# 4_-Analog_Input.net
KiCad netlist of a schematic drawn in Altium Designer
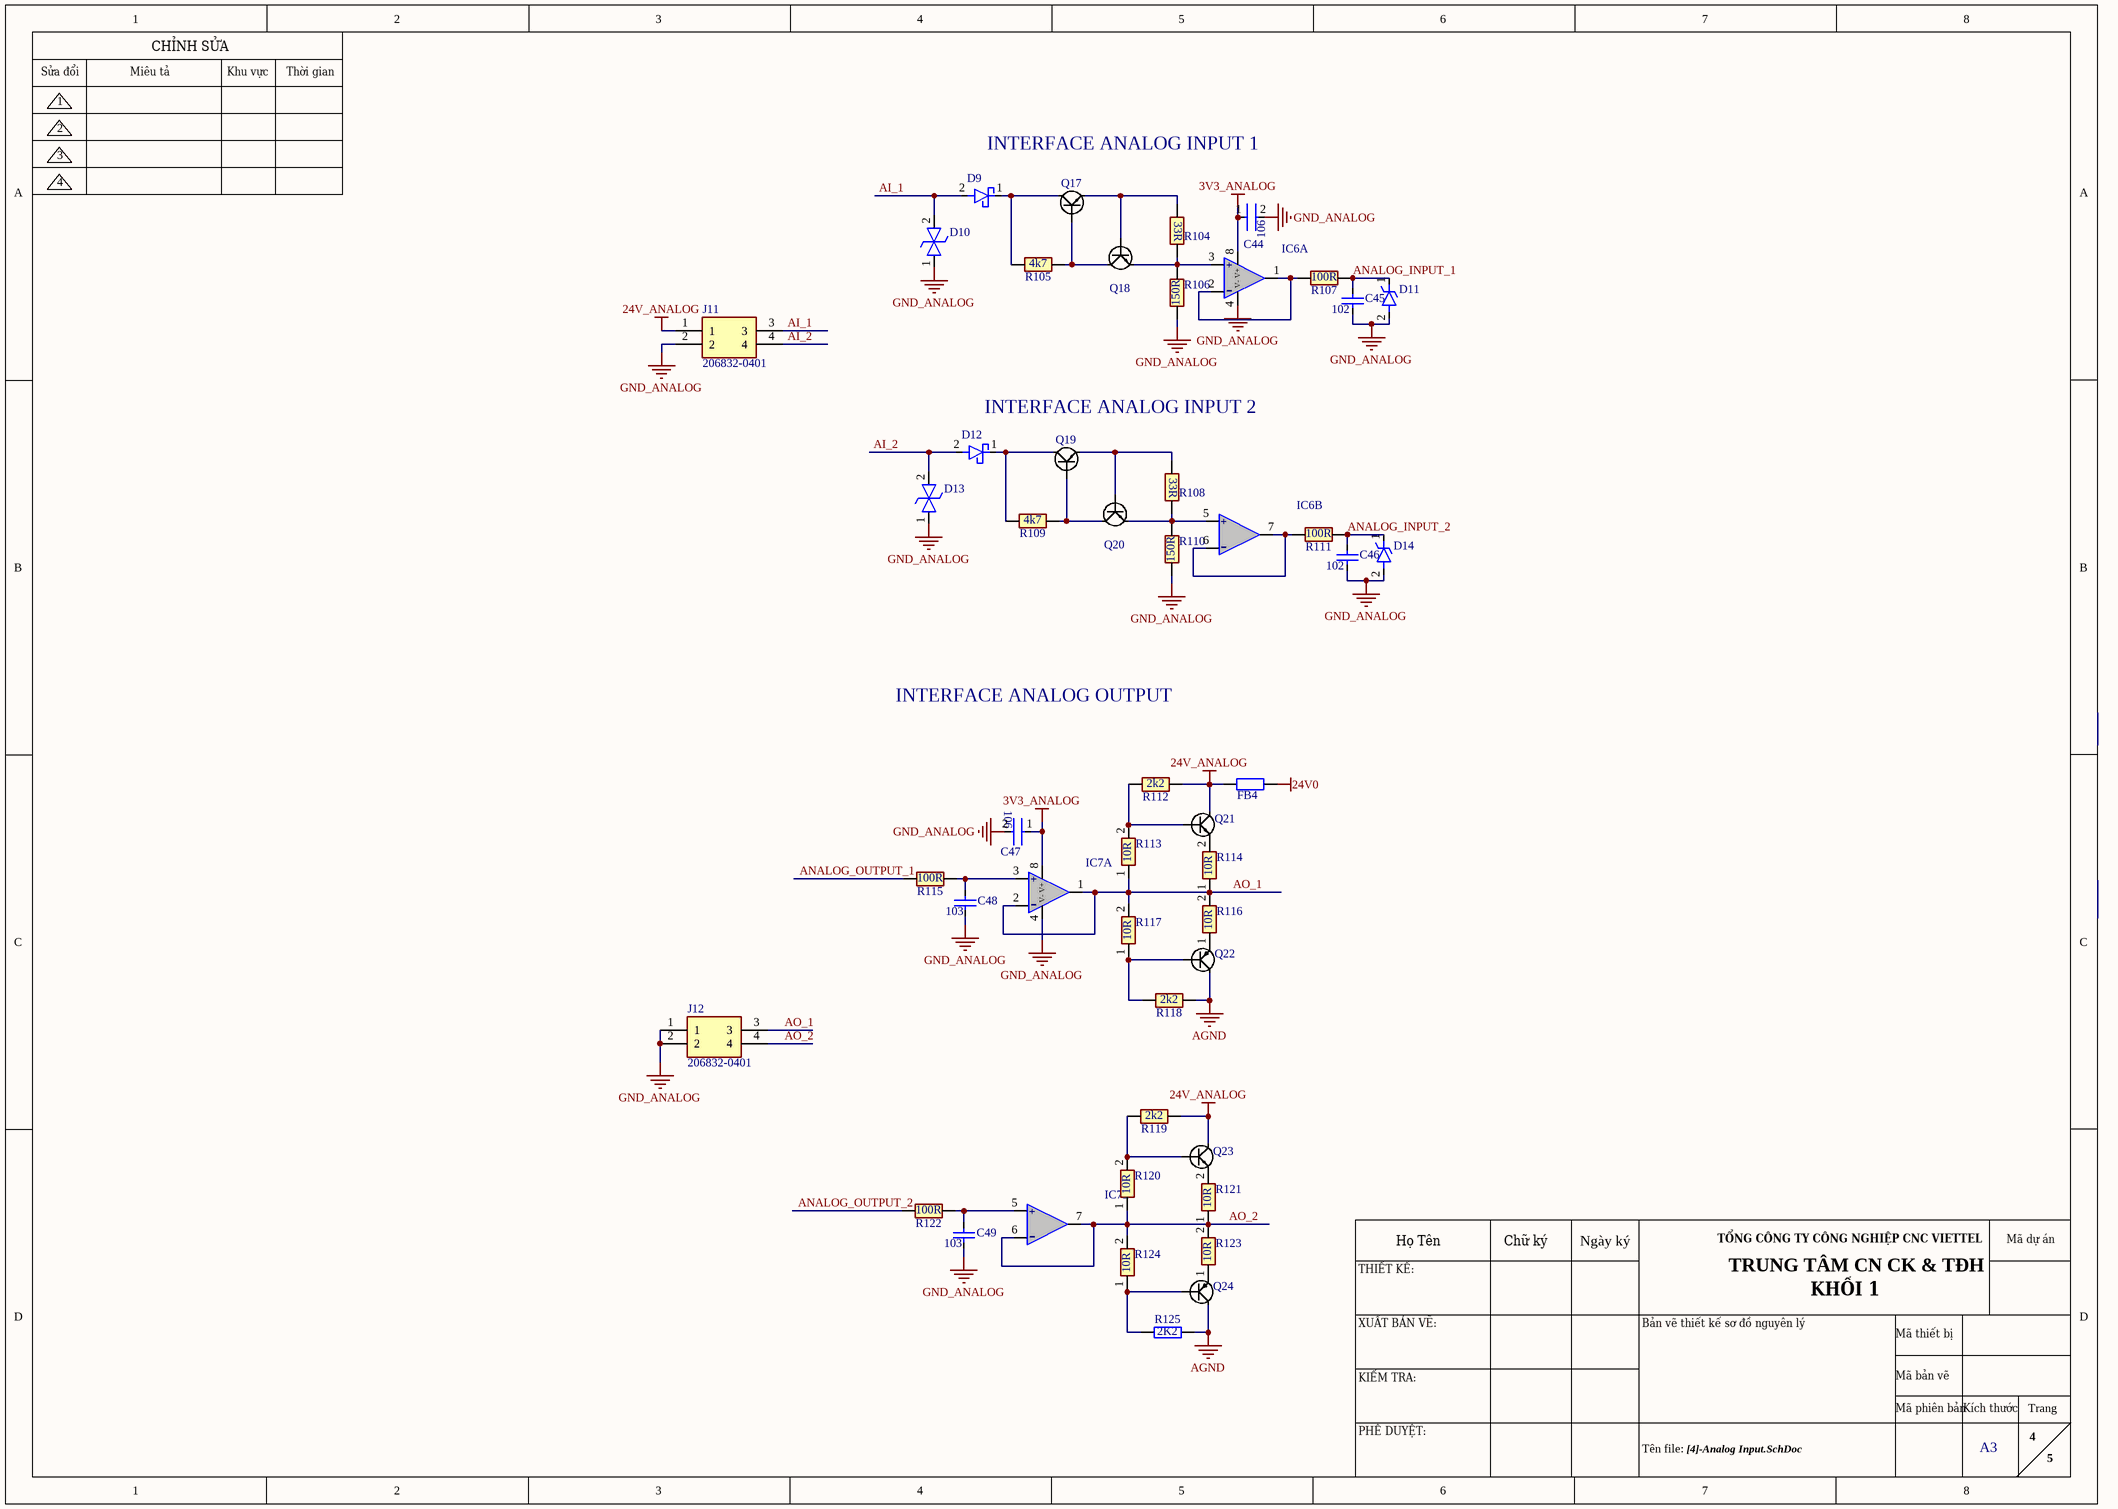
[diagram p0: [4]-Analog Input.SchDoc]

(export (version "E")
  (design (tool "Eeschema 10.0.6"))
  (components
    (comp (ref "C44")
      (value "C0603_106_35V")
      (footprint "SamacSys:C0603")
      (description "Multilayer Ceramic Capacitors MLCC - SMD/SMT 10 uF 35 VDC 20% 0603 X5R")
      (fields
        (field (name "MANUFACTURER_PART_NUMBER") "GRM188R6YA106MA73J")
        (field (name "MOUSER PART NUMBER") "81-GRM188R6YA106MA3J")
      )
      (libsource (lib "SamacSys") (part "C0603_106_35V"))
    )
    (comp (ref "C45")
      (value "C0603_102_50V")
      (footprint "SamacSys:C0603")
      (description "Multilayer Ceramic Capacitors MLCC - SMD/SMT 50V 1000pF X7R 0603 10%")
      (fields
        (field (name "MANUFACTURER_PART_NUMBER") "CC0603KRX7R9BB102")
        (field (name "MOUSER PART NUMBER") "603-CC603KRX7R9BB102")
      )
      (libsource (lib "SamacSys") (part "C0603_102_50V"))
    )
    (comp (ref "C46")
      (value "C0603_102_50V")
      (footprint "SamacSys:C0603")
      (description "Multilayer Ceramic Capacitors MLCC - SMD/SMT 50V 1000pF X7R 0603 10%")
      (fields
        (field (name "MANUFACTURER_PART_NUMBER") "CC0603KRX7R9BB102")
        (field (name "MOUSER PART NUMBER") "603-CC603KRX7R9BB102")
      )
      (libsource (lib "SamacSys") (part "C0603_102_50V"))
    )
    (comp (ref "C47")
      (value "C0603_106_35V")
      (footprint "SamacSys:C0603")
      (description "Multilayer Ceramic Capacitors MLCC - SMD/SMT 10 uF 35 VDC 20% 0603 X5R")
      (fields
        (field (name "MANUFACTURER_PART_NUMBER") "GRM188R6YA106MA73J")
        (field (name "MOUSER PART NUMBER") "81-GRM188R6YA106MA3J")
      )
      (libsource (lib "SamacSys") (part "C0603_106_35V"))
    )
    (comp (ref "C48")
      (value "C0603_103_50V")
      (footprint "SamacSys:C0603")
      (description "Multilayer Ceramic Capacitors MLCC - SMD/SMT 50V 0.01uF X7R 0603 10%")
      (fields
        (field (name "MANUFACTURER_PART_NUMBER") "CC0603KRX7R9BB103")
        (field (name "MOUSER PART NUMBER") "603-CC603KRX7R9BB103")
      )
      (libsource (lib "SamacSys") (part "C0603_103_50V"))
    )
    (comp (ref "C49")
      (value "C0603_103_50V")
      (footprint "SamacSys:C0603")
      (description "Multilayer Ceramic Capacitors MLCC - SMD/SMT 50V 0.01uF X7R 0603 10%")
      (fields
        (field (name "MANUFACTURER_PART_NUMBER") "CC0603KRX7R9BB103")
        (field (name "MOUSER PART NUMBER") "603-CC603KRX7R9BB103")
      )
      (libsource (lib "SamacSys") (part "C0603_103_50V"))
    )
    (comp (ref "D9")
      (value "SS36FA")
      (footprint "SamacSys:SOD-123FA-2")
      (description "Schottky Diodes & Rectifiers 60V 3A Schottky B arrier Rectifier")
      (fields (field (name "MOUSER PART NUMBER") "512-SS36FA"))
      (libsource (lib "SamacSys") (part "SS36FA"))
    )
    (comp (ref "D10")
      (value "SMCJ36CA_V6G")
      (footprint "SamacSys:DIONM7959X262N")
      (description "TVS Diode (Bi-directional)")
      (fields
        (field (name "MANUFACTURER_PART_NUMBER") "SMCJ36CA V6G")
        (field (name "MOUSER PART NUMBER") "821-SMCJ36CAV6G")
      )
      (libsource (lib "SamacSys") (part "SMCJ36CA_V6G"))
    )
    (comp (ref "D11")
      (value "MM3Z3V3B")
      (footprint "SamacSys:SOD323F")
      (description "Zener Diodes 3.3V 200mW 2%")
      (fields (field (name "MOUSER PART NUMBER") "512-MM3Z3V3B"))
      (libsource (lib "SamacSys") (part "MM3Z3V3B"))
    )
    (comp (ref "D12")
      (value "SS36FA")
      (footprint "SamacSys:SOD-123FA-2")
      (description "Schottky Diodes & Rectifiers 60V 3A Schottky B arrier Rectifier")
      (fields (field (name "MOUSER PART NUMBER") "512-SS36FA"))
      (libsource (lib "SamacSys") (part "SS36FA"))
    )
    (comp (ref "D13")
      (value "SMCJ36CA_V6G")
      (footprint "SamacSys:DIONM7959X262N")
      (description "TVS Diode (Bi-directional)")
      (fields
        (field (name "MANUFACTURER_PART_NUMBER") "SMCJ36CA V6G")
        (field (name "MOUSER PART NUMBER") "821-SMCJ36CAV6G")
      )
      (libsource (lib "SamacSys") (part "SMCJ36CA_V6G"))
    )
    (comp (ref "D14")
      (value "MM3Z3V3B")
      (footprint "SamacSys:SOD323F")
      (description "Zener Diodes 3.3V 200mW 2%")
      (fields (field (name "MOUSER PART NUMBER") "512-MM3Z3V3B"))
      (libsource (lib "SamacSys") (part "MM3Z3V3B"))
    )
    (comp (ref "FB4")
      (value "FERRIT_0805_1A")
      (footprint "SamacSys:FB0805")
      (fields
        (field (name "MANUFACTURER") "Laird-Signal Integrity Products")
        (field (name "PART NUMBER") "MI0805J102R-10")
      )
      (libsource (lib "SamacSys") (part "FERRIT_0805_1A"))
    )
    (comp (ref "IC6")
      (value "LM358DGKR")
      (footprint "SamacSys:VSSOP-8")
      (description "Integrated Circuit")
      (fields (field (name "MOUSER PART NUMBER") "595-LM358DGKR"))
      (libsource (lib "SamacSys") (part "LM358DGKR"))
    )
    (comp (ref "IC7")
      (value "LM358DGKR")
      (footprint "SamacSys:VSSOP-8")
      (description "Integrated Circuit")
      (fields (field (name "MOUSER PART NUMBER") "595-LM358DGKR"))
      (libsource (lib "SamacSys") (part "LM358DGKR"))
    )
    (comp (ref "J11")
      (value "206832-0401")
      (footprint "2068320401")
      (description "Headers & Wire Housings Micro-Fit Plus Vert HDR ASSY 2X2 Tin Lu")
      (fields (field (name "MOUSER PART NUMBER") "538-206832-0401"))
      (libsource (lib "SamacSys") (part "Header_2x2_male"))
    )
    (comp (ref "J12")
      (value "206832-0401")
      (footprint "2068320401")
      (description "Headers & Wire Housings Micro-Fit Plus Vert HDR ASSY 2X2 Tin Lu")
      (fields (field (name "MOUSER PART NUMBER") "538-206832-0401"))
      (libsource (lib "SamacSys") (part "Header_2x2_male"))
    )
    (comp (ref "Q17")
      (value "MMBT3904-TP")
      (footprint "SamacSys:SOT-23-3")
      (description "Transistor BJT NPN")
      (fields (field (name "MOUSER PART NUMBER") "833-MMBT3904-TP"))
      (libsource (lib "SamacSys") (part "MMBT3904-TP"))
    )
    (comp (ref "Q18")
      (value "MMBT3904-TP")
      (footprint "SamacSys:SOT-23-3")
      (description "Transistor BJT NPN")
      (fields (field (name "MOUSER PART NUMBER") "833-MMBT3904-TP"))
      (libsource (lib "SamacSys") (part "MMBT3904-TP"))
    )
    (comp (ref "Q19")
      (value "MMBT3904-TP")
      (footprint "SamacSys:SOT-23-3")
      (description "Transistor BJT NPN")
      (fields (field (name "MOUSER PART NUMBER") "833-MMBT3904-TP"))
      (libsource (lib "SamacSys") (part "MMBT3904-TP"))
    )
    (comp (ref "Q20")
      (value "MMBT3904-TP")
      (footprint "SamacSys:SOT-23-3")
      (description "Transistor BJT NPN")
      (fields (field (name "MOUSER PART NUMBER") "833-MMBT3904-TP"))
      (libsource (lib "SamacSys") (part "MMBT3904-TP"))
    )
    (comp (ref "Q21")
      (value "PMBT2222A,215")
      (footprint "SOT-23")
      (description "Bipolar (BJT) Transistor NPN 30 V 600 mA 300MHz 250 mW Surface Mount TO-236AB")
      (fields (field (name "MANUFACTURER") "Nexperia USA Inc."))
      (libsource (lib "SamacSys") (part "PMBT2222A,215"))
    )
    (comp (ref "Q22")
      (value "PMBT2907A,215")
      (footprint "SOT-23")
      (description "Bipolar (BJT) Transistor PNP 60 V 600 mA 200MHz 250 mW Surface Mount TO-236AB")
      (fields (field (name "MANUFACTURER") "Nexperia USA Inc."))
      (libsource (lib "SamacSys") (part "PMBT2907A,215"))
    )
    (comp (ref "Q23")
      (value "PMBT2222A,215")
      (footprint "SOT-23")
      (description "Bipolar (BJT) Transistor NPN 30 V 600 mA 300MHz 250 mW Surface Mount TO-236AB")
      (fields (field (name "MANUFACTURER") "Nexperia USA Inc."))
      (libsource (lib "SamacSys") (part "PMBT2222A,215"))
    )
    (comp (ref "Q24")
      (value "PMBT2907A,215")
      (footprint "SOT-23")
      (description "Bipolar (BJT) Transistor PNP 60 V 600 mA 200MHz 250 mW Surface Mount TO-236AB")
      (fields (field (name "MANUFACTURER") "Nexperia USA Inc."))
      (libsource (lib "SamacSys") (part "PMBT2907A,215"))
    )
    (comp (ref "R104")
      (value "R0603_33R")
      (footprint "SamacSys:RES-SMD-0603")
      (description "Resistor")
      (fields
        (field (name "MANUFACTURER_PART_NUMBER") "RC0603FR-0733RL")
        (field (name "MOUSER PART NUMBER") "603-RC0603FR-0733RL")
      )
      (libsource (lib "SamacSys") (part "R0603_33R"))
    )
    (comp (ref "R105")
      (value "R0603_4k7")
      (footprint "SamacSys:RES-SMD-0603")
      (description "Resistor")
      (fields
        (field (name "MANUFACTURER_PART_NUMBER") "ERJ-U3RD4701V")
        (field (name "MOUSER PART NUMBER") "667-ERJ-U3RD4701V")
      )
      (libsource (lib "SamacSys") (part "R0603_4k7"))
    )
    (comp (ref "R106")
      (value "R0603_150R")
      (footprint "SamacSys:RES-SMD-0603")
      (description "Resistor")
      (fields
        (field (name "MANUFACTURER_PART_NUMBER") "ERA-3AEB151V")
        (field (name "MOUSER PART NUMBER") "667-ERA-3AEB151V")
      )
      (libsource (lib "SamacSys") (part "R0603_150R"))
    )
    (comp (ref "R107")
      (value "100R")
      (footprint "SamacSys:RES-SMD-0603")
      (description "Thick Film Resistors - SMD 1/10watt 100ohms 5%")
      (fields
        (field (name "MANUFACTURER_PART_NUMBER") "CRCW0603100RJNEB")
        (field (name "MOUSER PART NUMBER") "71-CRCW0603100RJNEB")
      )
      (libsource (lib "SamacSys") (part "R0603_100R_75V"))
    )
    (comp (ref "R108")
      (value "R0603_33R")
      (footprint "SamacSys:RES-SMD-0603")
      (description "Resistor")
      (fields
        (field (name "MANUFACTURER_PART_NUMBER") "RC0603FR-0733RL")
        (field (name "MOUSER PART NUMBER") "603-RC0603FR-0733RL")
      )
      (libsource (lib "SamacSys") (part "R0603_33R"))
    )
    (comp (ref "R109")
      (value "R0603_4k7")
      (footprint "SamacSys:RES-SMD-0603")
      (description "Resistor")
      (fields
        (field (name "MANUFACTURER_PART_NUMBER") "ERJ-U3RD4701V")
        (field (name "MOUSER PART NUMBER") "667-ERJ-U3RD4701V")
      )
      (libsource (lib "SamacSys") (part "R0603_4k7"))
    )
    (comp (ref "R110")
      (value "R0603_150R")
      (footprint "SamacSys:RES-SMD-0603")
      (description "Resistor")
      (fields
        (field (name "MANUFACTURER_PART_NUMBER") "ERA-3AEB151V")
        (field (name "MOUSER PART NUMBER") "667-ERA-3AEB151V")
      )
      (libsource (lib "SamacSys") (part "R0603_150R"))
    )
    (comp (ref "R111")
      (value "100R")
      (footprint "SamacSys:RES-SMD-0603")
      (description "Thick Film Resistors - SMD 1/10watt 100ohms 5%")
      (fields
        (field (name "MANUFACTURER_PART_NUMBER") "CRCW0603100RJNEB")
        (field (name "MOUSER PART NUMBER") "71-CRCW0603100RJNEB")
      )
      (libsource (lib "SamacSys") (part "R0603_100R_75V"))
    )
    (comp (ref "R112")
      (value "R0603_2k2")
      (footprint "RES-SMD-0603")
      (description "Resistor")
      (fields
        (field (name "MANUFACTURER_PART_NUMBER") "ERJ-3EKF2201V")
        (field (name "MOUSER PART NUMBER") "667-ERJ-3EKF2201V")
      )
      (libsource (lib "SamacSys") (part "R0603_2k2"))
    )
    (comp (ref "R113")
      (value "R0603_10R")
      (footprint "SamacSys:RES-SMD-0603")
      (description "Thick Film Resistors - SMD 0603 10ohm 1% Anti-Surge AEC-Q200")
      (fields
        (field (name "MANUFACTURER_PART_NUMBER") "ERJ-PA3F10R0V")
        (field (name "MOUSER PART NUMBER") "667-ERJ-PA3F10R0V")
      )
      (libsource (lib "SamacSys") (part "R0603_10R"))
    )
    (comp (ref "R114")
      (value "R0603_10R")
      (footprint "SamacSys:RES-SMD-0603")
      (description "Thick Film Resistors - SMD 0603 10ohm 1% Anti-Surge AEC-Q200")
      (fields
        (field (name "MANUFACTURER_PART_NUMBER") "ERJ-PA3F10R0V")
        (field (name "MOUSER PART NUMBER") "667-ERJ-PA3F10R0V")
      )
      (libsource (lib "SamacSys") (part "R0603_10R"))
    )
    (comp (ref "R115")
      (value "100R")
      (footprint "SamacSys:RES-SMD-0603")
      (description "Thick Film Resistors - SMD 1/10watt 100ohms 5%")
      (fields
        (field (name "MANUFACTURER_PART_NUMBER") "CRCW0603100RJNEB")
        (field (name "MOUSER PART NUMBER") "71-CRCW0603100RJNEB")
      )
      (libsource (lib "SamacSys") (part "R0603_100R_75V"))
    )
    (comp (ref "R116")
      (value "R0603_10R")
      (footprint "SamacSys:RES-SMD-0603")
      (description "Thick Film Resistors - SMD 0603 10ohm 1% Anti-Surge AEC-Q200")
      (fields
        (field (name "MANUFACTURER_PART_NUMBER") "ERJ-PA3F10R0V")
        (field (name "MOUSER PART NUMBER") "667-ERJ-PA3F10R0V")
      )
      (libsource (lib "SamacSys") (part "R0603_10R"))
    )
    (comp (ref "R117")
      (value "R0603_10R")
      (footprint "SamacSys:RES-SMD-0603")
      (description "Thick Film Resistors - SMD 0603 10ohm 1% Anti-Surge AEC-Q200")
      (fields
        (field (name "MANUFACTURER_PART_NUMBER") "ERJ-PA3F10R0V")
        (field (name "MOUSER PART NUMBER") "667-ERJ-PA3F10R0V")
      )
      (libsource (lib "SamacSys") (part "R0603_10R"))
    )
    (comp (ref "R118")
      (value "R0603_2k2")
      (footprint "RES-SMD-0603")
      (description "Resistor")
      (fields
        (field (name "MANUFACTURER_PART_NUMBER") "ERJ-3EKF2201V")
        (field (name "MOUSER PART NUMBER") "667-ERJ-3EKF2201V")
      )
      (libsource (lib "SamacSys") (part "R0603_2k2"))
    )
    (comp (ref "R119")
      (value "R0603_2k2")
      (footprint "RES-SMD-0603")
      (description "Resistor")
      (fields
        (field (name "MANUFACTURER_PART_NUMBER") "ERJ-3EKF2201V")
        (field (name "MOUSER PART NUMBER") "667-ERJ-3EKF2201V")
      )
      (libsource (lib "SamacSys") (part "R0603_2k2"))
    )
    (comp (ref "R120")
      (value "R0603_10R")
      (footprint "SamacSys:RES-SMD-0603")
      (description "Thick Film Resistors - SMD 0603 10ohm 1% Anti-Surge AEC-Q200")
      (fields
        (field (name "MANUFACTURER_PART_NUMBER") "ERJ-PA3F10R0V")
        (field (name "MOUSER PART NUMBER") "667-ERJ-PA3F10R0V")
      )
      (libsource (lib "SamacSys") (part "R0603_10R"))
    )
    (comp (ref "R121")
      (value "R0603_10R")
      (footprint "SamacSys:RES-SMD-0603")
      (description "Thick Film Resistors - SMD 0603 10ohm 1% Anti-Surge AEC-Q200")
      (fields
        (field (name "MANUFACTURER_PART_NUMBER") "ERJ-PA3F10R0V")
        (field (name "MOUSER PART NUMBER") "667-ERJ-PA3F10R0V")
      )
      (libsource (lib "SamacSys") (part "R0603_10R"))
    )
    (comp (ref "R122")
      (value "100R")
      (footprint "SamacSys:RES-SMD-0603")
      (description "Thick Film Resistors - SMD 1/10watt 100ohms 5%")
      (fields
        (field (name "MANUFACTURER_PART_NUMBER") "CRCW0603100RJNEB")
        (field (name "MOUSER PART NUMBER") "71-CRCW0603100RJNEB")
      )
      (libsource (lib "SamacSys") (part "R0603_100R_75V"))
    )
    (comp (ref "R123")
      (value "R0603_10R")
      (footprint "SamacSys:RES-SMD-0603")
      (description "Thick Film Resistors - SMD 0603 10ohm 1% Anti-Surge AEC-Q200")
      (fields
        (field (name "MANUFACTURER_PART_NUMBER") "ERJ-PA3F10R0V")
        (field (name "MOUSER PART NUMBER") "667-ERJ-PA3F10R0V")
      )
      (libsource (lib "SamacSys") (part "R0603_10R"))
    )
    (comp (ref "R124")
      (value "R0603_10R")
      (footprint "SamacSys:RES-SMD-0603")
      (description "Thick Film Resistors - SMD 0603 10ohm 1% Anti-Surge AEC-Q200")
      (fields
        (field (name "MANUFACTURER_PART_NUMBER") "ERJ-PA3F10R0V")
        (field (name "MOUSER PART NUMBER") "667-ERJ-PA3F10R0V")
      )
      (libsource (lib "SamacSys") (part "R0603_10R"))
    )
    (comp (ref "R125")
      (value "2K2")
      (footprint "R0603")
      (description "2.2 kOhms ±1% 0.1W, 1/10W Chip Resistor 0603 (1608 Metric) Moisture Resistant Thick Film")
      (fields (field (name "MANUFACTURER") "YAGEO") (field (name "PART NUMBER") "RC0603FR-132K2L"))
      (libsource (lib "hoangdx_lib") (part "R0603_2K2"))
    )
  )
  (nets
    (net (code "1") (name "/AI_1") (class "Default")
      (node (ref "D10") (pin "2") (pinfunction "2_2") (pintype "passive"))
      (node (ref "D9") (pin "2") (pinfunction "A_2") (pintype "passive"))
      (node (ref "J11") (pin "3") (pinfunction "3_3") (pintype "passive"))
    )
    (net (code "2") (name "/AI_2") (class "Default")
      (node (ref "D12") (pin "2") (pinfunction "A_2") (pintype "passive"))
      (node (ref "D13") (pin "2") (pinfunction "2_2") (pintype "passive"))
      (node (ref "J11") (pin "4") (pinfunction "4_4") (pintype "passive"))
    )
    (net (code "3") (name "/ANALOG_INPUT_1") (class "Default")
      (node (ref "C45") (pin "1") (pinfunction "1_1") (pintype "passive"))
      (node (ref "D11") (pin "1") (pinfunction "K_1") (pintype "passive"))
      (node (ref "R107") (pin "2") (pinfunction "2_2") (pintype "passive"))
    )
    (net (code "4") (name "/ANALOG_INPUT_2") (class "Default")
      (node (ref "C46") (pin "1") (pinfunction "1_1") (pintype "passive"))
      (node (ref "D14") (pin "1") (pinfunction "K_1") (pintype "passive"))
      (node (ref "R111") (pin "2") (pinfunction "2_2") (pintype "passive"))
    )
    (net (code "5") (name "/ANALOG_OUTPUT_1") (class "Default")
      (node (ref "R115") (pin "1") (pinfunction "1_1") (pintype "passive"))
    )
    (net (code "6") (name "/ANALOG_OUTPUT_2") (class "Default")
      (node (ref "R122") (pin "1") (pinfunction "1_1") (pintype "passive"))
    )
    (net (code "7") (name "/AO_1") (class "Default")
      (node (ref "IC7") (pin "1") (pintype "passive"))
      (node (ref "IC7") (pin "2") (pintype "passive"))
      (node (ref "J12") (pin "3") (pinfunction "3_3") (pintype "passive"))
      (node (ref "R113") (pin "1") (pinfunction "1_1") (pintype "passive"))
      (node (ref "R114") (pin "1") (pinfunction "1_1") (pintype "passive"))
      (node (ref "R116") (pin "2") (pinfunction "2_2") (pintype "passive"))
      (node (ref "R117") (pin "2") (pinfunction "2_2") (pintype "passive"))
    )
    (net (code "8") (name "/AO_2") (class "Default")
      (node (ref "IC7") (pin "6") (pintype "passive"))
      (node (ref "IC7") (pin "7") (pintype "passive"))
      (node (ref "J12") (pin "4") (pinfunction "4_4") (pintype "passive"))
      (node (ref "R120") (pin "1") (pinfunction "1_1") (pintype "passive"))
      (node (ref "R121") (pin "1") (pinfunction "1_1") (pintype "passive"))
      (node (ref "R123") (pin "2") (pinfunction "2_2") (pintype "passive"))
      (node (ref "R124") (pin "2") (pinfunction "2_2") (pintype "passive"))
    )
    (net (code "9") (name "3V3_ANALOG") (class "Default")
      (node (ref "C44") (pin "1") (pinfunction "1_1") (pintype "passive"))
      (node (ref "C47") (pin "1") (pinfunction "1_1") (pintype "passive"))
      (node (ref "IC6") (pin "8") (pinfunction "V+_8") (pintype "passive"))
      (node (ref "IC7") (pin "8") (pinfunction "V+_8") (pintype "passive"))
    )
    (net (code "10") (name "24V0") (class "Default")
      (node (ref "FB4") (pin "2") (pinfunction "2_2") (pintype "passive"))
    )
    (net (code "11") (name "24V_ANALOG") (class "Default")
      (node (ref "FB4") (pin "1") (pinfunction "1_1") (pintype "passive"))
      (node (ref "J11") (pin "1") (pinfunction "1_1") (pintype "passive"))
      (node (ref "Q21") (pin "3") (pinfunction "C_3") (pintype "passive"))
      (node (ref "Q23") (pin "3") (pinfunction "C_3") (pintype "passive"))
      (node (ref "R112") (pin "2") (pinfunction "2_2") (pintype "passive"))
      (node (ref "R119") (pin "2") (pinfunction "2_2") (pintype "passive"))
    )
    (net (code "12") (name "AGND") (class "Default")
      (node (ref "Q22") (pin "3") (pinfunction "C_3") (pintype "passive"))
      (node (ref "Q24") (pin "3") (pinfunction "C_3") (pintype "passive"))
      (node (ref "R118") (pin "2") (pinfunction "2_2") (pintype "passive"))
      (node (ref "R125") (pin "2") (pinfunction "2_2") (pintype "passive"))
    )
    (net (code "13") (name "GND_ANALOG") (class "Default")
      (node (ref "C44") (pin "2") (pinfunction "2_2") (pintype "passive"))
      (node (ref "C45") (pin "2") (pinfunction "2_2") (pintype "passive"))
      (node (ref "C46") (pin "2") (pinfunction "2_2") (pintype "passive"))
      (node (ref "C47") (pin "2") (pinfunction "2_2") (pintype "passive"))
      (node (ref "C48") (pin "2") (pinfunction "2_2") (pintype "passive"))
      (node (ref "C49") (pin "2") (pinfunction "2_2") (pintype "passive"))
      (node (ref "D11") (pin "2") (pinfunction "A_2") (pintype "passive"))
      (node (ref "D14") (pin "2") (pinfunction "A_2") (pintype "passive"))
      (node (ref "IC6") (pin "4") (pinfunction "V-_4") (pintype "passive"))
      (node (ref "IC7") (pin "4") (pinfunction "V-_4") (pintype "passive"))
      (node (ref "J11") (pin "2") (pinfunction "2_2") (pintype "passive"))
      (node (ref "J12") (pin "1") (pinfunction "1_1") (pintype "passive"))
      (node (ref "J12") (pin "2") (pinfunction "2_2") (pintype "passive"))
      (node (ref "R106") (pin "1") (pinfunction "1_1") (pintype "passive"))
      (node (ref "R110") (pin "1") (pinfunction "1_1") (pintype "passive"))
    )
    (net (code "14") (name "Net-(C48-Pad1)") (class "Default")
      (node (ref "C48") (pin "1") (pinfunction "1_1") (pintype "passive"))
      (node (ref "IC7") (pin "3") (pintype "passive"))
      (node (ref "R115") (pin "2") (pinfunction "2_2") (pintype "passive"))
    )
    (net (code "15") (name "Net-(C49-Pad1)") (class "Default")
      (node (ref "C49") (pin "1") (pinfunction "1_1") (pintype "passive"))
      (node (ref "IC7") (pin "5") (pintype "passive"))
      (node (ref "R122") (pin "2") (pinfunction "2_2") (pintype "passive"))
    )
    (net (code "16") (name "Net-(D9-K)") (class "Default")
      (node (ref "D9") (pin "1") (pinfunction "K_1") (pintype "passive"))
      (node (ref "Q17") (pin "3") (pinfunction "C_3") (pintype "passive"))
      (node (ref "R105") (pin "1") (pinfunction "1_1") (pintype "passive"))
    )
    (net (code "17") (name "Net-(D12-K)") (class "Default")
      (node (ref "D12") (pin "1") (pinfunction "K_1") (pintype "passive"))
      (node (ref "Q19") (pin "3") (pinfunction "C_3") (pintype "passive"))
      (node (ref "R109") (pin "1") (pinfunction "1_1") (pintype "passive"))
    )
    (net (code "18") (name "Net-(IC6-Pad1)") (class "Default")
      (node (ref "IC6") (pin "1") (pintype "passive"))
      (node (ref "IC6") (pin "2") (pintype "passive"))
      (node (ref "R107") (pin "1") (pinfunction "1_1") (pintype "passive"))
    )
    (net (code "19") (name "Net-(IC6-Pad6)") (class "Default")
      (node (ref "IC6") (pin "6") (pintype "passive"))
      (node (ref "IC6") (pin "7") (pintype "passive"))
      (node (ref "R111") (pin "1") (pinfunction "1_1") (pintype "passive"))
    )
    (net (code "20") (name "Net-(Q17-B)") (class "Default")
      (node (ref "Q17") (pin "1") (pinfunction "B_1") (pintype "passive"))
      (node (ref "Q18") (pin "3") (pinfunction "C_3") (pintype "passive"))
      (node (ref "R105") (pin "2") (pinfunction "2_2") (pintype "passive"))
    )
    (net (code "21") (name "Net-(Q17-E)") (class "Default")
      (node (ref "Q17") (pin "2") (pinfunction "E_2") (pintype "passive"))
      (node (ref "Q18") (pin "1") (pinfunction "B_1") (pintype "passive"))
      (node (ref "R104") (pin "1") (pinfunction "1_1") (pintype "passive"))
    )
    (net (code "22") (name "Net-(Q18-E)") (class "Default")
      (node (ref "IC6") (pin "3") (pintype "passive"))
      (node (ref "Q18") (pin "2") (pinfunction "E_2") (pintype "passive"))
      (node (ref "R104") (pin "2") (pinfunction "2_2") (pintype "passive"))
      (node (ref "R106") (pin "2") (pinfunction "2_2") (pintype "passive"))
    )
    (net (code "23") (name "Net-(Q19-B)") (class "Default")
      (node (ref "Q19") (pin "1") (pinfunction "B_1") (pintype "passive"))
      (node (ref "Q20") (pin "3") (pinfunction "C_3") (pintype "passive"))
      (node (ref "R109") (pin "2") (pinfunction "2_2") (pintype "passive"))
    )
    (net (code "24") (name "Net-(Q19-E)") (class "Default")
      (node (ref "Q19") (pin "2") (pinfunction "E_2") (pintype "passive"))
      (node (ref "Q20") (pin "1") (pinfunction "B_1") (pintype "passive"))
      (node (ref "R108") (pin "1") (pinfunction "1_1") (pintype "passive"))
    )
    (net (code "25") (name "Net-(Q20-E)") (class "Default")
      (node (ref "IC6") (pin "5") (pintype "passive"))
      (node (ref "Q20") (pin "2") (pinfunction "E_2") (pintype "passive"))
      (node (ref "R108") (pin "2") (pinfunction "2_2") (pintype "passive"))
      (node (ref "R110") (pin "2") (pinfunction "2_2") (pintype "passive"))
    )
    (net (code "26") (name "Net-(Q21-B)") (class "Default")
      (node (ref "Q21") (pin "1") (pinfunction "B_1") (pintype "passive"))
      (node (ref "R112") (pin "1") (pinfunction "1_1") (pintype "passive"))
      (node (ref "R113") (pin "2") (pinfunction "2_2") (pintype "passive"))
    )
    (net (code "27") (name "Net-(Q21-E)") (class "Default")
      (node (ref "Q21") (pin "2") (pinfunction "E_2") (pintype "passive"))
      (node (ref "R114") (pin "2") (pinfunction "2_2") (pintype "passive"))
    )
    (net (code "28") (name "Net-(Q22-B)") (class "Default")
      (node (ref "Q22") (pin "1") (pinfunction "B_1") (pintype "passive"))
      (node (ref "R117") (pin "1") (pinfunction "1_1") (pintype "passive"))
      (node (ref "R118") (pin "1") (pinfunction "1_1") (pintype "passive"))
    )
    (net (code "29") (name "Net-(Q22-E)") (class "Default")
      (node (ref "Q22") (pin "2") (pinfunction "E_2") (pintype "passive"))
      (node (ref "R116") (pin "1") (pinfunction "1_1") (pintype "passive"))
    )
    (net (code "30") (name "Net-(Q23-B)") (class "Default")
      (node (ref "Q23") (pin "1") (pinfunction "B_1") (pintype "passive"))
      (node (ref "R119") (pin "1") (pinfunction "1_1") (pintype "passive"))
      (node (ref "R120") (pin "2") (pinfunction "2_2") (pintype "passive"))
    )
    (net (code "31") (name "Net-(Q23-E)") (class "Default")
      (node (ref "Q23") (pin "2") (pinfunction "E_2") (pintype "passive"))
      (node (ref "R121") (pin "2") (pinfunction "2_2") (pintype "passive"))
    )
    (net (code "32") (name "Net-(Q24-B)") (class "Default")
      (node (ref "Q24") (pin "1") (pinfunction "B_1") (pintype "passive"))
      (node (ref "R124") (pin "1") (pinfunction "1_1") (pintype "passive"))
      (node (ref "R125") (pin "1") (pinfunction "1_1") (pintype "passive"))
    )
    (net (code "33") (name "Net-(Q24-E)") (class "Default")
      (node (ref "Q24") (pin "2") (pinfunction "E_2") (pintype "passive"))
      (node (ref "R123") (pin "1") (pinfunction "1_1") (pintype "passive"))
    )
    (net (code "34") (name "unconnected-(D10-Pad1)") (class "Default")
      (node (ref "D10") (pin "1") (pinfunction "1_1") (pintype "passive"))
    )
    (net (code "35") (name "unconnected-(D13-Pad1)") (class "Default")
      (node (ref "D13") (pin "1") (pinfunction "1_1") (pintype "passive"))
    )
  )
)
